# DDR4.net
KiCad netlist of a schematic drawn in Altium Designer
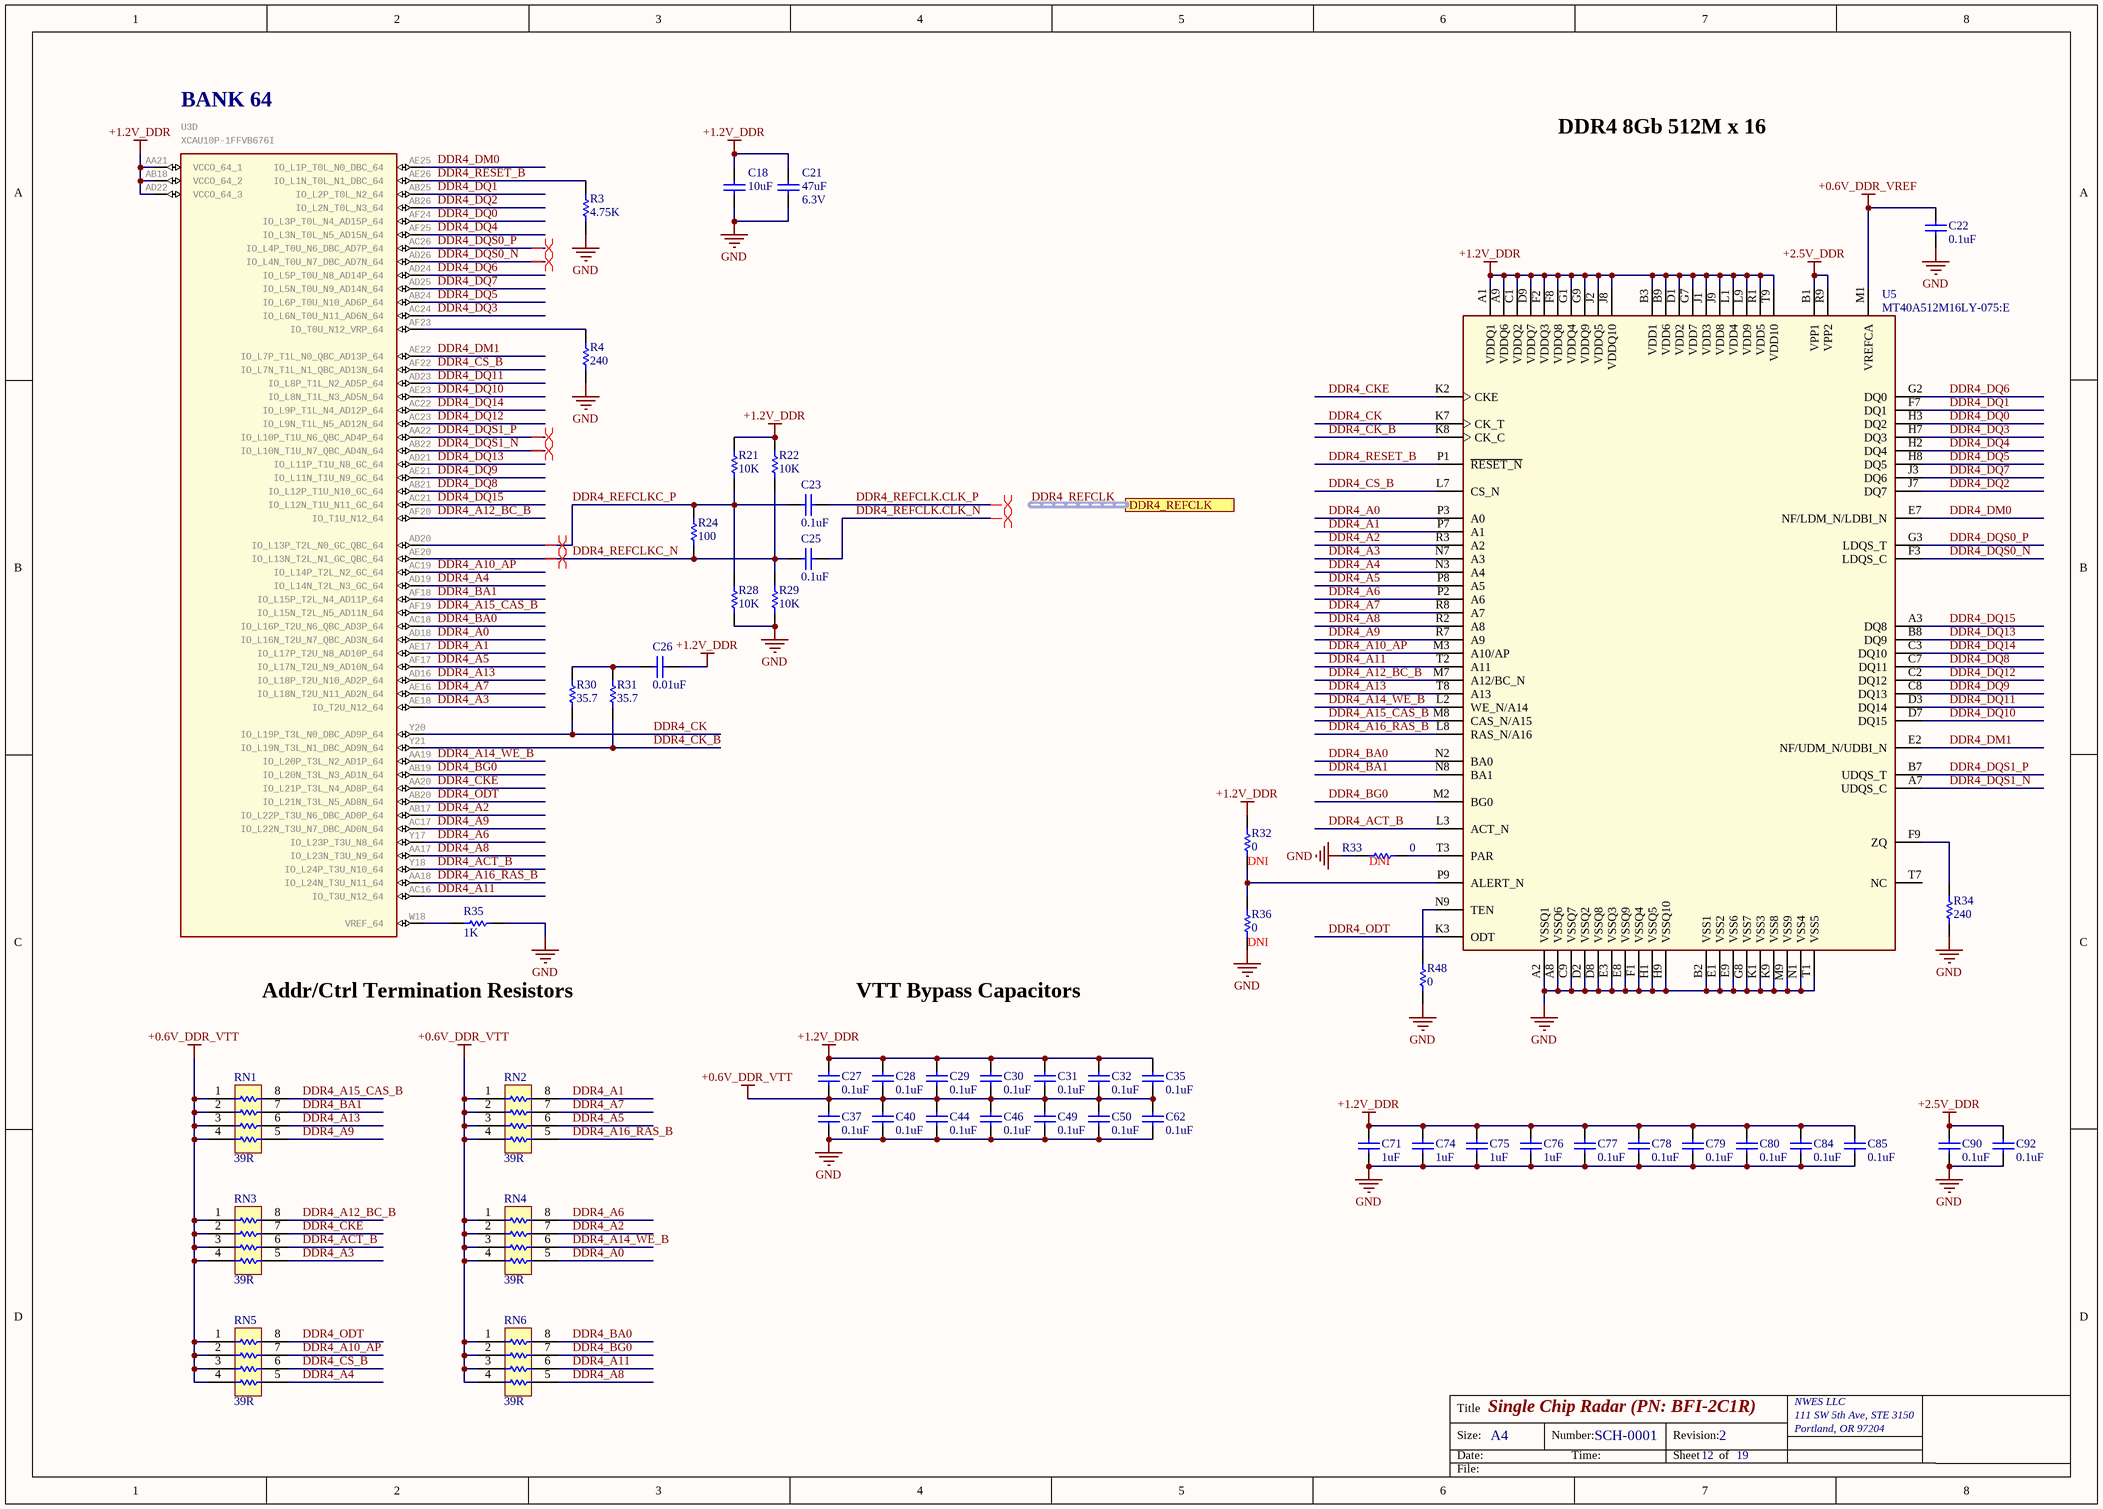
[diagram p0: DDR4.SchDoc]

(export (version "E")
  (design (tool "Eeschema 10.0.6"))
  (components
    (comp (ref "C18")
      (value "10uF")
      (footprint "CAPC1005X90")
      (description "CAP CER 10UF 10V X5R 0402")
      (fields
        (field (name "MANUFACTURER PART NUMBER") "CL05A106MP8NUB8")
        (field (name "MANUFACTURER") "Samsung Electro-Mechanics")
      )
      (libsource (lib "Radar FPGA RF") (part "CAP CER 10UF 10V X5R 0402"))
    )
    (comp (ref "C21")
      (value "47uF")
      (footprint "CAP-1206")
      (description "CAP CER 47UF 6.3V X5R 0805")
      (fields
        (field (name "MANUFACTURER") "Samsung")
        (field (name "MANUFACTURER PART NUMBER") "CL21A476MQYNNNE")
        (field (name "VOLTAGE RATING") "6.3V")
      )
      (libsource (lib "Radar FPGA RF") (part "CAP CER 47UF 6.3V X5R 0805"))
    )
    (comp (ref "C22")
      (value "0.1uF")
      (footprint "CAPC1005X55USR")
      (description "CAP CER 0.1UF 25V X5R 0402")
      (fields
        (field (name "MANUFACTURER PART NUMBER") "CL05A104KA5NNNC")
        (field (name "MANUFACTURER") "Samsung Electro-Mechanics")
      )
      (libsource (lib "Radar FPGA RF") (part "CAP CER 0.1UF 25V X5R 0402"))
    )
    (comp (ref "C23")
      (value "0.1uF")
      (footprint "CAPC1005X55USR")
      (description "CAP CER 0.1UF 25V X5R 0402")
      (fields
        (field (name "MANUFACTURER PART NUMBER") "CL05A104KA5NNNC")
        (field (name "MANUFACTURER") "Samsung Electro-Mechanics")
      )
      (libsource (lib "Radar FPGA RF") (part "CAP CER 0.1UF 25V X5R 0402"))
    )
    (comp (ref "C25")
      (value "0.1uF")
      (footprint "CAPC1005X55USR")
      (description "CAP CER 0.1UF 25V X5R 0402")
      (fields
        (field (name "MANUFACTURER PART NUMBER") "CL05A104KA5NNNC")
        (field (name "MANUFACTURER") "Samsung Electro-Mechanics")
      )
      (libsource (lib "Radar FPGA RF") (part "CAP CER 0.1UF 25V X5R 0402"))
    )
    (comp (ref "C26")
      (value "0.01uF")
      (footprint "CAPC1005X55USR")
      (description "CAP CER 10000PF 50V X7R 0402")
      (fields
        (field (name "MANUFACTURER PART NUMBER") "GCM155R71H103KA55D")
        (field (name "MANUFACTURER") "Murata Electronics")
      )
      (libsource (lib "Radar FPGA RF") (part "CAP CER 0.01uF 50V X7R 0402"))
    )
    (comp (ref "C27")
      (value "0.1uF")
      (footprint "CAPC1005X55USR")
      (description "CAP CER 0.1UF 25V X5R 0402")
      (fields
        (field (name "MANUFACTURER PART NUMBER") "CL05A104KA5NNNC")
        (field (name "MANUFACTURER") "Samsung Electro-Mechanics")
      )
      (libsource (lib "Radar FPGA RF") (part "CAP CER 0.1UF 25V X5R 0402"))
    )
    (comp (ref "C28")
      (value "0.1uF")
      (footprint "CAPC1005X55USR")
      (description "CAP CER 0.1UF 25V X5R 0402")
      (fields
        (field (name "MANUFACTURER PART NUMBER") "CL05A104KA5NNNC")
        (field (name "MANUFACTURER") "Samsung Electro-Mechanics")
      )
      (libsource (lib "Radar FPGA RF") (part "CAP CER 0.1UF 25V X5R 0402"))
    )
    (comp (ref "C29")
      (value "0.1uF")
      (footprint "CAPC1005X55USR")
      (description "CAP CER 0.1UF 25V X5R 0402")
      (fields
        (field (name "MANUFACTURER PART NUMBER") "CL05A104KA5NNNC")
        (field (name "MANUFACTURER") "Samsung Electro-Mechanics")
      )
      (libsource (lib "Radar FPGA RF") (part "CAP CER 0.1UF 25V X5R 0402"))
    )
    (comp (ref "C30")
      (value "0.1uF")
      (footprint "CAPC1005X55USR")
      (description "CAP CER 0.1UF 25V X5R 0402")
      (fields
        (field (name "MANUFACTURER PART NUMBER") "CL05A104KA5NNNC")
        (field (name "MANUFACTURER") "Samsung Electro-Mechanics")
      )
      (libsource (lib "Radar FPGA RF") (part "CAP CER 0.1UF 25V X5R 0402"))
    )
    (comp (ref "C31")
      (value "0.1uF")
      (footprint "CAPC1005X55USR")
      (description "CAP CER 0.1UF 25V X5R 0402")
      (fields
        (field (name "MANUFACTURER PART NUMBER") "CL05A104KA5NNNC")
        (field (name "MANUFACTURER") "Samsung Electro-Mechanics")
      )
      (libsource (lib "Radar FPGA RF") (part "CAP CER 0.1UF 25V X5R 0402"))
    )
    (comp (ref "C32")
      (value "0.1uF")
      (footprint "CAPC1005X55USR")
      (description "CAP CER 0.1UF 25V X5R 0402")
      (fields
        (field (name "MANUFACTURER PART NUMBER") "CL05A104KA5NNNC")
        (field (name "MANUFACTURER") "Samsung Electro-Mechanics")
      )
      (libsource (lib "Radar FPGA RF") (part "CAP CER 0.1UF 25V X5R 0402"))
    )
    (comp (ref "C35")
      (value "0.1uF")
      (footprint "CAPC1005X55USR")
      (description "CAP CER 0.1UF 25V X5R 0402")
      (fields
        (field (name "MANUFACTURER PART NUMBER") "CL05A104KA5NNNC")
        (field (name "MANUFACTURER") "Samsung Electro-Mechanics")
      )
      (libsource (lib "Radar FPGA RF") (part "CAP CER 0.1UF 25V X5R 0402"))
    )
    (comp (ref "C37")
      (value "0.1uF")
      (footprint "CAPC1005X55USR")
      (description "CAP CER 0.1UF 25V X5R 0402")
      (fields
        (field (name "MANUFACTURER PART NUMBER") "CL05A104KA5NNNC")
        (field (name "MANUFACTURER") "Samsung Electro-Mechanics")
      )
      (libsource (lib "Radar FPGA RF") (part "CAP CER 0.1UF 25V X5R 0402"))
    )
    (comp (ref "C40")
      (value "0.1uF")
      (footprint "CAPC1005X55USR")
      (description "CAP CER 0.1UF 25V X5R 0402")
      (fields
        (field (name "MANUFACTURER PART NUMBER") "CL05A104KA5NNNC")
        (field (name "MANUFACTURER") "Samsung Electro-Mechanics")
      )
      (libsource (lib "Radar FPGA RF") (part "CAP CER 0.1UF 25V X5R 0402"))
    )
    (comp (ref "C44")
      (value "0.1uF")
      (footprint "CAPC1005X55USR")
      (description "CAP CER 0.1UF 25V X5R 0402")
      (fields
        (field (name "MANUFACTURER PART NUMBER") "CL05A104KA5NNNC")
        (field (name "MANUFACTURER") "Samsung Electro-Mechanics")
      )
      (libsource (lib "Radar FPGA RF") (part "CAP CER 0.1UF 25V X5R 0402"))
    )
    (comp (ref "C46")
      (value "0.1uF")
      (footprint "CAPC1005X55USR")
      (description "CAP CER 0.1UF 25V X5R 0402")
      (fields
        (field (name "MANUFACTURER PART NUMBER") "CL05A104KA5NNNC")
        (field (name "MANUFACTURER") "Samsung Electro-Mechanics")
      )
      (libsource (lib "Radar FPGA RF") (part "CAP CER 0.1UF 25V X5R 0402"))
    )
    (comp (ref "C49")
      (value "0.1uF")
      (footprint "CAPC1005X55USR")
      (description "CAP CER 0.1UF 25V X5R 0402")
      (fields
        (field (name "MANUFACTURER PART NUMBER") "CL05A104KA5NNNC")
        (field (name "MANUFACTURER") "Samsung Electro-Mechanics")
      )
      (libsource (lib "Radar FPGA RF") (part "CAP CER 0.1UF 25V X5R 0402"))
    )
    (comp (ref "C50")
      (value "0.1uF")
      (footprint "CAPC1005X55USR")
      (description "CAP CER 0.1UF 25V X5R 0402")
      (fields
        (field (name "MANUFACTURER PART NUMBER") "CL05A104KA5NNNC")
        (field (name "MANUFACTURER") "Samsung Electro-Mechanics")
      )
      (libsource (lib "Radar FPGA RF") (part "CAP CER 0.1UF 25V X5R 0402"))
    )
    (comp (ref "C62")
      (value "0.1uF")
      (footprint "CAPC1005X55USR")
      (description "CAP CER 0.1UF 25V X5R 0402")
      (fields
        (field (name "MANUFACTURER PART NUMBER") "CL05A104KA5NNNC")
        (field (name "MANUFACTURER") "Samsung Electro-Mechanics")
      )
      (libsource (lib "Radar FPGA RF") (part "CAP CER 0.1UF 25V X5R 0402"))
    )
    (comp (ref "C71")
      (value "1uF")
      (footprint "CAPC1005X55USR")
      (description "CAP CER 1UF 25V X5R 0402")
      (fields
        (field (name "MANUFACTURER PART NUMBER") "GRM155R61E105MA12D")
        (field (name "MANUFACTURER") "Murata Electronics")
      )
      (libsource (lib "Radar FPGA RF") (part "CAP CER 1UF 25V X5R 0402"))
    )
    (comp (ref "C74")
      (value "1uF")
      (footprint "CAPC1005X55USR")
      (description "CAP CER 1UF 25V X5R 0402")
      (fields
        (field (name "MANUFACTURER PART NUMBER") "GRM155R61E105MA12D")
        (field (name "MANUFACTURER") "Murata Electronics")
      )
      (libsource (lib "Radar FPGA RF") (part "CAP CER 1UF 25V X5R 0402"))
    )
    (comp (ref "C75")
      (value "1uF")
      (footprint "CAPC1005X55USR")
      (description "CAP CER 1UF 25V X5R 0402")
      (fields
        (field (name "MANUFACTURER PART NUMBER") "GRM155R61E105MA12D")
        (field (name "MANUFACTURER") "Murata Electronics")
      )
      (libsource (lib "Radar FPGA RF") (part "CAP CER 1UF 25V X5R 0402"))
    )
    (comp (ref "C76")
      (value "1uF")
      (footprint "CAPC1005X55USR")
      (description "CAP CER 1UF 25V X5R 0402")
      (fields
        (field (name "MANUFACTURER PART NUMBER") "GRM155R61E105MA12D")
        (field (name "MANUFACTURER") "Murata Electronics")
      )
      (libsource (lib "Radar FPGA RF") (part "CAP CER 1UF 25V X5R 0402"))
    )
    (comp (ref "C77")
      (value "0.1uF")
      (footprint "CAPC1005X55USR")
      (description "CAP CER 0.1UF 25V X5R 0402")
      (fields
        (field (name "MANUFACTURER PART NUMBER") "CL05A104KA5NNNC")
        (field (name "MANUFACTURER") "Samsung Electro-Mechanics")
      )
      (libsource (lib "Radar FPGA RF") (part "CAP CER 0.1UF 25V X5R 0402"))
    )
    (comp (ref "C78")
      (value "0.1uF")
      (footprint "CAPC1005X55USR")
      (description "CAP CER 0.1UF 25V X5R 0402")
      (fields
        (field (name "MANUFACTURER PART NUMBER") "CL05A104KA5NNNC")
        (field (name "MANUFACTURER") "Samsung Electro-Mechanics")
      )
      (libsource (lib "Radar FPGA RF") (part "CAP CER 0.1UF 25V X5R 0402"))
    )
    (comp (ref "C79")
      (value "0.1uF")
      (footprint "CAPC1005X55USR")
      (description "CAP CER 0.1UF 25V X5R 0402")
      (fields
        (field (name "MANUFACTURER PART NUMBER") "CL05A104KA5NNNC")
        (field (name "MANUFACTURER") "Samsung Electro-Mechanics")
      )
      (libsource (lib "Radar FPGA RF") (part "CAP CER 0.1UF 25V X5R 0402"))
    )
    (comp (ref "C80")
      (value "0.1uF")
      (footprint "CAPC1005X55USR")
      (description "CAP CER 0.1UF 25V X5R 0402")
      (fields
        (field (name "MANUFACTURER PART NUMBER") "CL05A104KA5NNNC")
        (field (name "MANUFACTURER") "Samsung Electro-Mechanics")
      )
      (libsource (lib "Radar FPGA RF") (part "CAP CER 0.1UF 25V X5R 0402"))
    )
    (comp (ref "C84")
      (value "0.1uF")
      (footprint "CAPC1005X55USR")
      (description "CAP CER 0.1UF 25V X5R 0402")
      (fields
        (field (name "MANUFACTURER PART NUMBER") "CL05A104KA5NNNC")
        (field (name "MANUFACTURER") "Samsung Electro-Mechanics")
      )
      (libsource (lib "Radar FPGA RF") (part "CAP CER 0.1UF 25V X5R 0402"))
    )
    (comp (ref "C85")
      (value "0.1uF")
      (footprint "CAPC1005X55USR")
      (description "CAP CER 0.1UF 25V X5R 0402")
      (fields
        (field (name "MANUFACTURER PART NUMBER") "CL05A104KA5NNNC")
        (field (name "MANUFACTURER") "Samsung Electro-Mechanics")
      )
      (libsource (lib "Radar FPGA RF") (part "CAP CER 0.1UF 25V X5R 0402"))
    )
    (comp (ref "C90")
      (value "0.1uF")
      (footprint "CAPC1005X55USR")
      (description "CAP CER 0.1UF 25V X5R 0402")
      (fields
        (field (name "MANUFACTURER PART NUMBER") "CL05A104KA5NNNC")
        (field (name "MANUFACTURER") "Samsung Electro-Mechanics")
      )
      (libsource (lib "Radar FPGA RF") (part "CAP CER 0.1UF 25V X5R 0402"))
    )
    (comp (ref "C92")
      (value "0.1uF")
      (footprint "CAPC1005X55USR")
      (description "CAP CER 0.1UF 25V X5R 0402")
      (fields
        (field (name "MANUFACTURER PART NUMBER") "CL05A104KA5NNNC")
        (field (name "MANUFACTURER") "Samsung Electro-Mechanics")
      )
      (libsource (lib "Radar FPGA RF") (part "CAP CER 0.1UF 25V X5R 0402"))
    )
    (comp (ref "R3")
      (value "4.75K")
      (footprint "RESC1005X40USR")
      (description "RES 4.75K OHM 1% 1/16W 0402")
      (fields
        (field (name "MANUFACTURER") "YAGEO")
        (field (name "MANUFACTURER PART NUMBER") "RC0402FR-074K75L")
      )
      (libsource (lib "Radar FPGA RF") (part "RES 4.75K OHM 1% 1/16W 0402"))
    )
    (comp (ref "R4")
      (value "240")
      (footprint "RESC1005X40USR")
      (description "RES 240 OHM 1% 1/16W 0402")
      (fields
        (field (name "MANUFACTURER") "YAGEO")
        (field (name "MANUFACTURER PART NUMBER") "RC0402FR-07240RL")
      )
      (libsource (lib "Radar FPGA RF") (part "RES 240 OHM 1% 1/16W 0402"))
    )
    (comp (ref "R21")
      (value "10K")
      (footprint "RESC1005X40USR")
      (description "RES 10K OHM 1% 1/16W 0402")
      (fields
        (field (name "MANUFACTURER") "YAGEO")
        (field (name "MANUFACTURER PART NUMBER") "RC0402FR-0710KL")
      )
      (libsource (lib "Radar FPGA RF") (part "RES 10K OHM 1% 1/16W 0402"))
    )
    (comp (ref "R22")
      (value "10K")
      (footprint "RESC1005X40USR")
      (description "RES 10K OHM 1% 1/16W 0402")
      (fields
        (field (name "MANUFACTURER") "YAGEO")
        (field (name "MANUFACTURER PART NUMBER") "RC0402FR-0710KL")
      )
      (libsource (lib "Radar FPGA RF") (part "RES 10K OHM 1% 1/16W 0402"))
    )
    (comp (ref "R24")
      (value "100")
      (footprint "RESC1005X40USR")
      (description "RES 100 OHM 1% 1/16W 0402")
      (fields
        (field (name "MANUFACTURER") "YAGEO")
        (field (name "MANUFACTURER PART NUMBER") "RC0402FR-07100RL")
      )
      (libsource (lib "Radar FPGA RF") (part "RES 100 OHM 1% 1/16W 0402"))
    )
    (comp (ref "R28")
      (value "10K")
      (footprint "RESC1005X40USR")
      (description "RES 10K OHM 1% 1/16W 0402")
      (fields
        (field (name "MANUFACTURER") "YAGEO")
        (field (name "MANUFACTURER PART NUMBER") "RC0402FR-0710KL")
      )
      (libsource (lib "Radar FPGA RF") (part "RES 10K OHM 1% 1/16W 0402"))
    )
    (comp (ref "R29")
      (value "10K")
      (footprint "RESC1005X40USR")
      (description "RES 10K OHM 1% 1/16W 0402")
      (fields
        (field (name "MANUFACTURER") "YAGEO")
        (field (name "MANUFACTURER PART NUMBER") "RC0402FR-0710KL")
      )
      (libsource (lib "Radar FPGA RF") (part "RES 10K OHM 1% 1/16W 0402"))
    )
    (comp (ref "R30")
      (value "35.7")
      (footprint "RESC1005X40USR")
      (description "RES 35.7 OHM 1% 1/16W 0402")
      (fields
        (field (name "MANUFACTURER") "YAGEO")
        (field (name "MANUFACTURER PART NUMBER") "RC0402FR-0735R7L")
      )
      (libsource (lib "Radar FPGA RF") (part "RES 35.7 OHM 1% 1/16W 0402"))
    )
    (comp (ref "R31")
      (value "35.7")
      (footprint "RESC1005X40USR")
      (description "RES 35.7 OHM 1% 1/16W 0402")
      (fields
        (field (name "MANUFACTURER") "YAGEO")
        (field (name "MANUFACTURER PART NUMBER") "RC0402FR-0735R7L")
      )
      (libsource (lib "Radar FPGA RF") (part "RES 35.7 OHM 1% 1/16W 0402"))
    )
    (comp (ref "R32")
      (value "0")
      (footprint "RESC1005X40USR")
      (description "RES 0 OHM JUMPER 1/16W 0402")
      (fields
        (field (name "MANUFACTURER") "Yageo")
        (field (name "MANUFACTURER PART NUMBER") "RC0402JR-070RL")
      )
      (libsource (lib "Radar FPGA RF") (part "RES 0 OHM JUMPER 1/16W 0402"))
    )
    (comp (ref "R33")
      (value "0")
      (footprint "RESC1005X40USR")
      (description "RES 0 OHM JUMPER 1/16W 0402")
      (fields
        (field (name "MANUFACTURER") "Yageo")
        (field (name "MANUFACTURER PART NUMBER") "RC0402JR-070RL")
      )
      (libsource (lib "Radar FPGA RF") (part "RES 0 OHM JUMPER 1/16W 0402"))
    )
    (comp (ref "R34")
      (value "240")
      (footprint "RESC1005X40USR")
      (description "RES 240 OHM 1% 1/16W 0402")
      (fields
        (field (name "MANUFACTURER") "YAGEO")
        (field (name "MANUFACTURER PART NUMBER") "RC0402FR-07240RL")
      )
      (libsource (lib "Radar FPGA RF") (part "RES 240 OHM 1% 1/16W 0402"))
    )
    (comp (ref "R35")
      (value "1K")
      (footprint "RESC1005X40USR")
      (description "RES 1K OHM 1% 1/16W 0402")
      (fields
        (field (name "MANUFACTURER") "YAGEO")
        (field (name "MANUFACTURER PART NUMBER") "RC0402FR-071KL")
      )
      (libsource (lib "Radar FPGA RF") (part "RES 1K OHM 1% 1/16W 0402"))
    )
    (comp (ref "R36")
      (value "0")
      (footprint "RESC1005X40USR")
      (description "RES 0 OHM JUMPER 1/16W 0402")
      (fields
        (field (name "MANUFACTURER") "Yageo")
        (field (name "MANUFACTURER PART NUMBER") "RC0402JR-070RL")
      )
      (libsource (lib "Radar FPGA RF") (part "RES 0 OHM JUMPER 1/16W 0402"))
    )
    (comp (ref "R48")
      (value "0")
      (footprint "RESC1005X40USR")
      (description "RES 0 OHM JUMPER 1/16W 0402")
      (fields
        (field (name "MANUFACTURER") "Yageo")
        (field (name "MANUFACTURER PART NUMBER") "RC0402JR-070RL")
      )
      (libsource (lib "Radar FPGA RF") (part "RES 0 OHM JUMPER 1/16W 0402"))
    )
    (comp (ref "RN1")
      (value "39R")
      (footprint "RESCAXS50P100X200X45-8NA")
      (description "Res Thick Film Array 39 Ohm 5% ±200ppm/°C ISOL Molded 8-Pin 0804(4 X 0402) Concave SMD T/R")
      (fields
        (field (name "MANUFACTURER") "Panasonic")
        (field (name "MANUFACTURER PART NUMBER") "EXB-N8V390JX")
      )
      (libsource (lib "Radar FPGA RF") (part "RES ARRAY 4 RES 39 OHM 0804"))
    )
    (comp (ref "RN2")
      (value "39R")
      (footprint "RESCAXS50P100X200X45-8NA")
      (description "Res Thick Film Array 39 Ohm 5% ±200ppm/°C ISOL Molded 8-Pin 0804(4 X 0402) Concave SMD T/R")
      (fields
        (field (name "MANUFACTURER") "Panasonic")
        (field (name "MANUFACTURER PART NUMBER") "EXB-N8V390JX")
      )
      (libsource (lib "Radar FPGA RF") (part "RES ARRAY 4 RES 39 OHM 0804"))
    )
    (comp (ref "RN3")
      (value "39R")
      (footprint "RESCAXS50P100X200X45-8NA")
      (description "Res Thick Film Array 39 Ohm 5% ±200ppm/°C ISOL Molded 8-Pin 0804(4 X 0402) Concave SMD T/R")
      (fields
        (field (name "MANUFACTURER") "Panasonic")
        (field (name "MANUFACTURER PART NUMBER") "EXB-N8V390JX")
      )
      (libsource (lib "Radar FPGA RF") (part "RES ARRAY 4 RES 39 OHM 0804"))
    )
    (comp (ref "RN4")
      (value "39R")
      (footprint "RESCAXS50P100X200X45-8NA")
      (description "Res Thick Film Array 39 Ohm 5% ±200ppm/°C ISOL Molded 8-Pin 0804(4 X 0402) Concave SMD T/R")
      (fields
        (field (name "MANUFACTURER") "Panasonic")
        (field (name "MANUFACTURER PART NUMBER") "EXB-N8V390JX")
      )
      (libsource (lib "Radar FPGA RF") (part "RES ARRAY 4 RES 39 OHM 0804"))
    )
    (comp (ref "RN5")
      (value "39R")
      (footprint "RESCAXS50P100X200X45-8NA")
      (description "Res Thick Film Array 39 Ohm 5% ±200ppm/°C ISOL Molded 8-Pin 0804(4 X 0402) Concave SMD T/R")
      (fields
        (field (name "MANUFACTURER") "Panasonic")
        (field (name "MANUFACTURER PART NUMBER") "EXB-N8V390JX")
      )
      (libsource (lib "Radar FPGA RF") (part "RES ARRAY 4 RES 39 OHM 0804"))
    )
    (comp (ref "RN6")
      (value "39R")
      (footprint "RESCAXS50P100X200X45-8NA")
      (description "Res Thick Film Array 39 Ohm 5% ±200ppm/°C ISOL Molded 8-Pin 0804(4 X 0402) Concave SMD T/R")
      (fields
        (field (name "MANUFACTURER") "Panasonic")
        (field (name "MANUFACTURER PART NUMBER") "EXB-N8V390JX")
      )
      (libsource (lib "Radar FPGA RF") (part "RES ARRAY 4 RES 39 OHM 0804"))
    )
    (comp (ref "U3")
      (value "XCAU10P-1FFVB676I")
      (footprint "676-FCBGA (27x27)")
      (description "IC FPGA ARTIXUP 676BGA")
      (fields (field (name "MANUFACTURER") "AMD Xilinx"))
      (libsource (lib "LL") (part "XCAU10P-1FFVB676I"))
    )
    (comp (ref "U5")
      (value "MT40A512M16LY-075:E")
      (footprint "BGA96C80P6X16_1350X750X110")
      (description "DRAM Chip DDR4 SDRAM 8Gbit 512Mx16 1.2V 96-Pin FBGA Tray")
      (fields (field (name "MF") "Micron Technology"))
      (libsource (lib "XEM8320") (part "MT40A512M16LY-075{colon}E"))
    )
  )
  (nets
    (net (code "2") (name "+0.6V_DDR_VREF") (class "Default")
      (node (ref "C22") (pin "2") (pinfunction "2_2") (pintype "passive"))
      (node (ref "U5") (pin "M1") (pinfunction "VREFCA_M1") (pintype "passive"))
    )
    (net (code "3") (name "+0.6V_DDR_VTT") (class "Default")
      (node (ref "C27") (pin "1") (pinfunction "1_1") (pintype "passive"))
      (node (ref "C28") (pin "1") (pinfunction "1_1") (pintype "passive"))
      (node (ref "C29") (pin "1") (pinfunction "1_1") (pintype "passive"))
      (node (ref "C30") (pin "1") (pinfunction "1_1") (pintype "passive"))
      (node (ref "C31") (pin "1") (pinfunction "1_1") (pintype "passive"))
      (node (ref "C32") (pin "1") (pinfunction "1_1") (pintype "passive"))
      (node (ref "C35") (pin "1") (pinfunction "1_1") (pintype "passive"))
      (node (ref "C37") (pin "2") (pinfunction "2_2") (pintype "passive"))
      (node (ref "C40") (pin "2") (pinfunction "2_2") (pintype "passive"))
      (node (ref "C44") (pin "2") (pinfunction "2_2") (pintype "passive"))
      (node (ref "C46") (pin "2") (pinfunction "2_2") (pintype "passive"))
      (node (ref "C49") (pin "2") (pinfunction "2_2") (pintype "passive"))
      (node (ref "C50") (pin "2") (pinfunction "2_2") (pintype "passive"))
      (node (ref "C62") (pin "2") (pinfunction "2_2") (pintype "passive"))
      (node (ref "RN1") (pin "1") (pinfunction "1_1") (pintype "passive"))
      (node (ref "RN1") (pin "2") (pinfunction "2_2") (pintype "passive"))
      (node (ref "RN1") (pin "3") (pinfunction "3_3") (pintype "passive"))
      (node (ref "RN1") (pin "4") (pinfunction "4_4") (pintype "passive"))
      (node (ref "RN2") (pin "1") (pinfunction "1_1") (pintype "passive"))
      (node (ref "RN2") (pin "2") (pinfunction "2_2") (pintype "passive"))
      (node (ref "RN2") (pin "3") (pinfunction "3_3") (pintype "passive"))
      (node (ref "RN2") (pin "4") (pinfunction "4_4") (pintype "passive"))
      (node (ref "RN3") (pin "1") (pinfunction "1_1") (pintype "passive"))
      (node (ref "RN3") (pin "2") (pinfunction "2_2") (pintype "passive"))
      (node (ref "RN3") (pin "3") (pinfunction "3_3") (pintype "passive"))
      (node (ref "RN3") (pin "4") (pinfunction "4_4") (pintype "passive"))
      (node (ref "RN4") (pin "1") (pinfunction "1_1") (pintype "passive"))
      (node (ref "RN4") (pin "2") (pinfunction "2_2") (pintype "passive"))
      (node (ref "RN4") (pin "3") (pinfunction "3_3") (pintype "passive"))
      (node (ref "RN4") (pin "4") (pinfunction "4_4") (pintype "passive"))
      (node (ref "RN5") (pin "1") (pinfunction "1_1") (pintype "passive"))
      (node (ref "RN5") (pin "2") (pinfunction "2_2") (pintype "passive"))
      (node (ref "RN5") (pin "3") (pinfunction "3_3") (pintype "passive"))
      (node (ref "RN5") (pin "4") (pinfunction "4_4") (pintype "passive"))
      (node (ref "RN6") (pin "1") (pinfunction "1_1") (pintype "passive"))
      (node (ref "RN6") (pin "2") (pinfunction "2_2") (pintype "passive"))
      (node (ref "RN6") (pin "3") (pinfunction "3_3") (pintype "passive"))
      (node (ref "RN6") (pin "4") (pinfunction "4_4") (pintype "passive"))
    )
    (net (code "4") (name "+1.2V_DDR") (class "Default")
      (node (ref "C18") (pin "2") (pinfunction "2_2") (pintype "passive"))
      (node (ref "C21") (pin "1") (pinfunction "1_1") (pintype "passive"))
      (node (ref "C26") (pin "2") (pinfunction "2_2") (pintype "passive"))
      (node (ref "C27") (pin "2") (pinfunction "2_2") (pintype "passive"))
      (node (ref "C28") (pin "2") (pinfunction "2_2") (pintype "passive"))
      (node (ref "C29") (pin "2") (pinfunction "2_2") (pintype "passive"))
      (node (ref "C30") (pin "2") (pinfunction "2_2") (pintype "passive"))
      (node (ref "C31") (pin "2") (pinfunction "2_2") (pintype "passive"))
      (node (ref "C32") (pin "2") (pinfunction "2_2") (pintype "passive"))
      (node (ref "C35") (pin "2") (pinfunction "2_2") (pintype "passive"))
      (node (ref "C71") (pin "2") (pinfunction "2_2") (pintype "passive"))
      (node (ref "C74") (pin "2") (pinfunction "2_2") (pintype "passive"))
      (node (ref "C75") (pin "2") (pinfunction "2_2") (pintype "passive"))
      (node (ref "C76") (pin "2") (pinfunction "2_2") (pintype "passive"))
      (node (ref "C77") (pin "2") (pinfunction "2_2") (pintype "passive"))
      (node (ref "C78") (pin "2") (pinfunction "2_2") (pintype "passive"))
      (node (ref "C79") (pin "2") (pinfunction "2_2") (pintype "passive"))
      (node (ref "C80") (pin "2") (pinfunction "2_2") (pintype "passive"))
      (node (ref "C84") (pin "2") (pinfunction "2_2") (pintype "passive"))
      (node (ref "C85") (pin "2") (pinfunction "2_2") (pintype "passive"))
      (node (ref "R21") (pin "2") (pinfunction "2_2") (pintype "passive"))
      (node (ref "R22") (pin "2") (pinfunction "2_2") (pintype "passive"))
      (node (ref "R32") (pin "1") (pinfunction "1_1") (pintype "passive"))
      (node (ref "U3") (pin "AA21") (pinfunction "VCCO_64_1_AA21") (pintype "bidirectional"))
      (node (ref "U3") (pin "AB18") (pinfunction "VCCO_64_2_AB18") (pintype "bidirectional"))
      (node (ref "U3") (pin "AD22") (pinfunction "VCCO_64_3_AD22") (pintype "bidirectional"))
      (node (ref "U5") (pin "A1") (pinfunction "VDDQ1_A1") (pintype "passive"))
      (node (ref "U5") (pin "A9") (pinfunction "VDDQ6_A9") (pintype "passive"))
      (node (ref "U5") (pin "B3") (pinfunction "VDD1_B3") (pintype "passive"))
      (node (ref "U5") (pin "B9") (pinfunction "VDD6_B9") (pintype "passive"))
      (node (ref "U5") (pin "C1") (pinfunction "VDDQ2_C1") (pintype "passive"))
      (node (ref "U5") (pin "D1") (pinfunction "VDD2_D1") (pintype "passive"))
      (node (ref "U5") (pin "D9") (pinfunction "VDDQ7_D9") (pintype "passive"))
      (node (ref "U5") (pin "F2") (pinfunction "VDDQ3_F2") (pintype "passive"))
      (node (ref "U5") (pin "F8") (pinfunction "VDDQ8_F8") (pintype "passive"))
      (node (ref "U5") (pin "G1") (pinfunction "VDDQ4_G1") (pintype "passive"))
      (node (ref "U5") (pin "G7") (pinfunction "VDD7_G7") (pintype "passive"))
      (node (ref "U5") (pin "G9") (pinfunction "VDDQ9_G9") (pintype "passive"))
      (node (ref "U5") (pin "J1") (pinfunction "VDD3_J1") (pintype "passive"))
      (node (ref "U5") (pin "J2") (pinfunction "VDDQ5_J2") (pintype "passive"))
      (node (ref "U5") (pin "J8") (pinfunction "VDDQ10_J8") (pintype "passive"))
      (node (ref "U5") (pin "J9") (pinfunction "VDD8_J9") (pintype "passive"))
      (node (ref "U5") (pin "L1") (pinfunction "VDD4_L1") (pintype "passive"))
      (node (ref "U5") (pin "L9") (pinfunction "VDD9_L9") (pintype "passive"))
      (node (ref "U5") (pin "R1") (pinfunction "VDD5_R1") (pintype "passive"))
      (node (ref "U5") (pin "T9") (pinfunction "VDD10_T9") (pintype "passive"))
    )
    (net (code "5") (name "+2.5V_DDR") (class "Default")
      (node (ref "C90") (pin "2") (pinfunction "2_2") (pintype "passive"))
      (node (ref "C92") (pin "2") (pinfunction "2_2") (pintype "passive"))
      (node (ref "U5") (pin "B1") (pinfunction "VPP1_B1") (pintype "passive"))
      (node (ref "U5") (pin "R9") (pinfunction "VPP2_R9") (pintype "passive"))
    )
    (net (code "6") (name "/DDR4_A0") (class "Default")
      (node (ref "RN4") (pin "5") (pinfunction "5_5") (pintype "passive"))
      (node (ref "U3") (pin "AD18") (pinfunction "IO_L16N_T2U_N7_QBC_AD3N_64_AD18") (pintype "bidirectional"))
      (node (ref "U5") (pin "P3") (pinfunction "A0_P3") (pintype "passive"))
    )
    (net (code "7") (name "/DDR4_A1") (class "Default")
      (node (ref "RN2") (pin "8") (pinfunction "8_8") (pintype "passive"))
      (node (ref "U3") (pin "AE17") (pinfunction "IO_L17P_T2U_N8_AD10P_64_AE17") (pintype "bidirectional"))
      (node (ref "U5") (pin "P7") (pinfunction "A1_P7") (pintype "passive"))
    )
    (net (code "8") (name "/DDR4_A2") (class "Default")
      (node (ref "RN4") (pin "7") (pinfunction "7_7") (pintype "passive"))
      (node (ref "U3") (pin "AB17") (pinfunction "IO_L22P_T3U_N6_DBC_AD0P_64_AB17") (pintype "bidirectional"))
      (node (ref "U5") (pin "R3") (pinfunction "A2_R3") (pintype "passive"))
    )
    (net (code "9") (name "/DDR4_A3") (class "Default")
      (node (ref "RN3") (pin "5") (pinfunction "5_5") (pintype "passive"))
      (node (ref "U3") (pin "AE18") (pinfunction "IO_T2U_N12_64_AE18") (pintype "bidirectional"))
      (node (ref "U5") (pin "N7") (pinfunction "A3_N7") (pintype "passive"))
    )
    (net (code "10") (name "/DDR4_A4") (class "Default")
      (node (ref "RN5") (pin "5") (pinfunction "5_5") (pintype "passive"))
      (node (ref "U3") (pin "AD19") (pinfunction "IO_L14N_T2L_N3_GC_64_AD19") (pintype "bidirectional"))
      (node (ref "U5") (pin "N3") (pinfunction "A4_N3") (pintype "passive"))
    )
    (net (code "11") (name "/DDR4_A5") (class "Default")
      (node (ref "RN2") (pin "6") (pinfunction "6_6") (pintype "passive"))
      (node (ref "U3") (pin "AF17") (pinfunction "IO_L17N_T2U_N9_AD10N_64_AF17") (pintype "bidirectional"))
      (node (ref "U5") (pin "P8") (pinfunction "A5_P8") (pintype "passive"))
    )
    (net (code "12") (name "/DDR4_A6") (class "Default")
      (node (ref "RN4") (pin "8") (pinfunction "8_8") (pintype "passive"))
      (node (ref "U3") (pin "Y17") (pinfunction "IO_L23P_T3U_N8_64_Y17") (pintype "bidirectional"))
      (node (ref "U5") (pin "P2") (pinfunction "A6_P2") (pintype "passive"))
    )
    (net (code "13") (name "/DDR4_A7") (class "Default")
      (node (ref "RN2") (pin "7") (pinfunction "7_7") (pintype "passive"))
      (node (ref "U3") (pin "AE16") (pinfunction "IO_L18N_T2U_N11_AD2N_64_AE16") (pintype "bidirectional"))
      (node (ref "U5") (pin "R8") (pinfunction "A7_R8") (pintype "passive"))
    )
    (net (code "14") (name "/DDR4_A8") (class "Default")
      (node (ref "RN6") (pin "5") (pinfunction "5_5") (pintype "passive"))
      (node (ref "U3") (pin "AA17") (pinfunction "IO_L23N_T3U_N9_64_AA17") (pintype "bidirectional"))
      (node (ref "U5") (pin "R2") (pinfunction "A8_R2") (pintype "passive"))
    )
    (net (code "15") (name "/DDR4_A9") (class "Default")
      (node (ref "RN1") (pin "5") (pinfunction "5_5") (pintype "passive"))
      (node (ref "U3") (pin "AC17") (pinfunction "IO_L22N_T3U_N7_DBC_AD0N_64_AC17") (pintype "bidirectional"))
      (node (ref "U5") (pin "R7") (pinfunction "A9_R7") (pintype "passive"))
    )
    (net (code "16") (name "/DDR4_A10_AP") (class "Default")
      (node (ref "RN5") (pin "7") (pinfunction "7_7") (pintype "passive"))
      (node (ref "U3") (pin "AC19") (pinfunction "IO_L14P_T2L_N2_GC_64_AC19") (pintype "bidirectional"))
      (node (ref "U5") (pin "M3") (pinfunction "A10/AP_M3") (pintype "passive"))
    )
    (net (code "17") (name "/DDR4_A11") (class "Default")
      (node (ref "RN6") (pin "6") (pinfunction "6_6") (pintype "passive"))
      (node (ref "U3") (pin "AC16") (pinfunction "IO_T3U_N12_64_AC16") (pintype "bidirectional"))
      (node (ref "U5") (pin "T2") (pinfunction "A11_T2") (pintype "passive"))
    )
    (net (code "18") (name "/DDR4_A12_BC_B") (class "Default")
      (node (ref "RN3") (pin "8") (pinfunction "8_8") (pintype "passive"))
      (node (ref "U3") (pin "AF20") (pinfunction "IO_T1U_N12_64_AF20") (pintype "bidirectional"))
      (node (ref "U5") (pin "M7") (pinfunction "A12/BC_N_M7") (pintype "passive"))
    )
    (net (code "19") (name "/DDR4_A13") (class "Default")
      (node (ref "RN1") (pin "6") (pinfunction "6_6") (pintype "passive"))
      (node (ref "U3") (pin "AD16") (pinfunction "IO_L18P_T2U_N10_AD2P_64_AD16") (pintype "bidirectional"))
      (node (ref "U5") (pin "T8") (pinfunction "A13_T8") (pintype "passive"))
    )
    (net (code "20") (name "/DDR4_A14_WE_B") (class "Default")
      (node (ref "RN4") (pin "6") (pinfunction "6_6") (pintype "passive"))
      (node (ref "U3") (pin "AA19") (pinfunction "IO_L20P_T3L_N2_AD1P_64_AA19") (pintype "bidirectional"))
      (node (ref "U5") (pin "L2") (pinfunction "WE_N/A14_L2") (pintype "passive"))
    )
    (net (code "21") (name "/DDR4_A15_CAS_B") (class "Default")
      (node (ref "RN1") (pin "8") (pinfunction "8_8") (pintype "passive"))
      (node (ref "U3") (pin "AF19") (pinfunction "IO_L15N_T2L_N5_AD11N_64_AF19") (pintype "bidirectional"))
      (node (ref "U5") (pin "M8") (pinfunction "CAS_N/A15_M8") (pintype "passive"))
    )
    (net (code "22") (name "/DDR4_A16_RAS_B") (class "Default")
      (node (ref "RN2") (pin "5") (pinfunction "5_5") (pintype "passive"))
      (node (ref "U3") (pin "AA18") (pinfunction "IO_L24N_T3U_N11_64_AA18") (pintype "bidirectional"))
      (node (ref "U5") (pin "L8") (pinfunction "RAS_N/A16_L8") (pintype "passive"))
    )
    (net (code "23") (name "/DDR4_ACT_B") (class "Default")
      (node (ref "RN3") (pin "6") (pinfunction "6_6") (pintype "passive"))
      (node (ref "U3") (pin "Y18") (pinfunction "IO_L24P_T3U_N10_64_Y18") (pintype "bidirectional"))
      (node (ref "U5") (pin "L3") (pinfunction "ACT_N_L3") (pintype "passive"))
    )
    (net (code "24") (name "/DDR4_BA0") (class "Default")
      (node (ref "RN6") (pin "8") (pinfunction "8_8") (pintype "passive"))
      (node (ref "U3") (pin "AC18") (pinfunction "IO_L16P_T2U_N6_QBC_AD3P_64_AC18") (pintype "bidirectional"))
      (node (ref "U5") (pin "N2") (pinfunction "BA0_N2") (pintype "passive"))
    )
    (net (code "25") (name "/DDR4_BA1") (class "Default")
      (node (ref "RN1") (pin "7") (pinfunction "7_7") (pintype "passive"))
      (node (ref "U3") (pin "AF18") (pinfunction "IO_L15P_T2L_N4_AD11P_64_AF18") (pintype "bidirectional"))
      (node (ref "U5") (pin "N8") (pinfunction "BA1_N8") (pintype "passive"))
    )
    (net (code "26") (name "/DDR4_BG0") (class "Default")
      (node (ref "RN6") (pin "7") (pinfunction "7_7") (pintype "passive"))
      (node (ref "U3") (pin "AB19") (pinfunction "IO_L20N_T3L_N3_AD1N_64_AB19") (pintype "bidirectional"))
      (node (ref "U5") (pin "M2") (pinfunction "BG0_M2") (pintype "passive"))
    )
    (net (code "27") (name "/DDR4_CK") (class "Default")
      (node (ref "R30") (pin "1") (pinfunction "1_1") (pintype "passive"))
      (node (ref "U3") (pin "Y20") (pinfunction "IO_L19P_T3L_N0_DBC_AD9P_64_Y20") (pintype "bidirectional"))
      (node (ref "U5") (pin "K7") (pinfunction "CK_T_K7") (pintype "passive"))
    )
    (net (code "28") (name "/DDR4_CKE") (class "Default")
      (node (ref "RN3") (pin "7") (pinfunction "7_7") (pintype "passive"))
      (node (ref "U3") (pin "AA20") (pinfunction "IO_L21P_T3L_N4_AD8P_64_AA20") (pintype "bidirectional"))
      (node (ref "U5") (pin "K2") (pinfunction "CKE_K2") (pintype "passive"))
    )
    (net (code "29") (name "/DDR4_CK_B") (class "Default")
      (node (ref "R31") (pin "1") (pinfunction "1_1") (pintype "passive"))
      (node (ref "U3") (pin "Y21") (pinfunction "IO_L19N_T3L_N1_DBC_AD9N_64_Y21") (pintype "bidirectional"))
      (node (ref "U5") (pin "K8") (pinfunction "CK_C_K8") (pintype "passive"))
    )
    (net (code "30") (name "/DDR4_CS_B") (class "Default")
      (node (ref "RN5") (pin "6") (pinfunction "6_6") (pintype "passive"))
      (node (ref "U3") (pin "AF22") (pinfunction "IO_L7N_T1L_N1_QBC_AD13N_64_AF22") (pintype "bidirectional"))
      (node (ref "U5") (pin "L7") (pinfunction "CS_N_L7") (pintype "passive"))
    )
    (net (code "31") (name "/DDR4_DM0") (class "Default")
      (node (ref "U3") (pin "AE25") (pinfunction "IO_L1P_T0L_N0_DBC_64_AE25") (pintype "bidirectional"))
      (node (ref "U5") (pin "E7") (pinfunction "NF/LDM_N/LDBI_N_E7") (pintype "passive"))
    )
    (net (code "32") (name "/DDR4_DM1") (class "Default")
      (node (ref "U3") (pin "AE22") (pinfunction "IO_L7P_T1L_N0_QBC_AD13P_64_AE22") (pintype "bidirectional"))
      (node (ref "U5") (pin "E2") (pinfunction "NF/UDM_N/UDBI_N_E2") (pintype "passive"))
    )
    (net (code "33") (name "/DDR4_DQ0") (class "Default")
      (node (ref "U3") (pin "AF24") (pinfunction "IO_L3P_T0L_N4_AD15P_64_AF24") (pintype "bidirectional"))
      (node (ref "U5") (pin "H3") (pinfunction "DQ2_H3") (pintype "passive"))
    )
    (net (code "34") (name "/DDR4_DQ1") (class "Default")
      (node (ref "U3") (pin "AB25") (pinfunction "IO_L2P_T0L_N2_64_AB25") (pintype "bidirectional"))
      (node (ref "U5") (pin "F7") (pinfunction "DQ1_F7") (pintype "passive"))
    )
    (net (code "35") (name "/DDR4_DQ2") (class "Default")
      (node (ref "U3") (pin "AB26") (pinfunction "IO_L2N_T0L_N3_64_AB26") (pintype "bidirectional"))
      (node (ref "U5") (pin "J7") (pinfunction "DQ7_J7") (pintype "passive"))
    )
    (net (code "36") (name "/DDR4_DQ3") (class "Default")
      (node (ref "U3") (pin "AC24") (pinfunction "IO_L6N_T0U_N11_AD6N_64_AC24") (pintype "bidirectional"))
      (node (ref "U5") (pin "H7") (pinfunction "DQ3_H7") (pintype "passive"))
    )
    (net (code "37") (name "/DDR4_DQ4") (class "Default")
      (node (ref "U3") (pin "AF25") (pinfunction "IO_L3N_T0L_N5_AD15N_64_AF25") (pintype "bidirectional"))
      (node (ref "U5") (pin "H2") (pinfunction "DQ4_H2") (pintype "passive"))
    )
    (net (code "38") (name "/DDR4_DQ5") (class "Default")
      (node (ref "U3") (pin "AB24") (pinfunction "IO_L6P_T0U_N10_AD6P_64_AB24") (pintype "bidirectional"))
      (node (ref "U5") (pin "H8") (pinfunction "DQ5_H8") (pintype "passive"))
    )
    (net (code "39") (name "/DDR4_DQ6") (class "Default")
      (node (ref "U3") (pin "AD24") (pinfunction "IO_L5P_T0U_N8_AD14P_64_AD24") (pintype "bidirectional"))
      (node (ref "U5") (pin "G2") (pinfunction "DQ0_G2") (pintype "passive"))
    )
    (net (code "40") (name "/DDR4_DQ7") (class "Default")
      (node (ref "U3") (pin "AD25") (pinfunction "IO_L5N_T0U_N9_AD14N_64_AD25") (pintype "bidirectional"))
      (node (ref "U5") (pin "J3") (pinfunction "DQ6_J3") (pintype "passive"))
    )
    (net (code "41") (name "/DDR4_DQ8") (class "Default")
      (node (ref "U3") (pin "AB21") (pinfunction "IO_L12P_T1U_N10_GC_64_AB21") (pintype "bidirectional"))
      (node (ref "U5") (pin "C7") (pinfunction "DQ11_C7") (pintype "passive"))
    )
    (net (code "42") (name "/DDR4_DQ9") (class "Default")
      (node (ref "U3") (pin "AE21") (pinfunction "IO_L11N_T1U_N9_GC_64_AE21") (pintype "bidirectional"))
      (node (ref "U5") (pin "C8") (pinfunction "DQ13_C8") (pintype "passive"))
    )
    (net (code "43") (name "/DDR4_DQ10") (class "Default")
      (node (ref "U3") (pin "AE23") (pinfunction "IO_L8N_T1L_N3_AD5N_64_AE23") (pintype "bidirectional"))
      (node (ref "U5") (pin "D7") (pinfunction "DQ15_D7") (pintype "passive"))
    )
    (net (code "44") (name "/DDR4_DQ11") (class "Default")
      (node (ref "U3") (pin "AD23") (pinfunction "IO_L8P_T1L_N2_AD5P_64_AD23") (pintype "bidirectional"))
      (node (ref "U5") (pin "D3") (pinfunction "DQ14_D3") (pintype "passive"))
    )
    (net (code "45") (name "/DDR4_DQ12") (class "Default")
      (node (ref "U3") (pin "AC23") (pinfunction "IO_L9N_T1L_N5_AD12N_64_AC23") (pintype "bidirectional"))
      (node (ref "U5") (pin "C2") (pinfunction "DQ12_C2") (pintype "passive"))
    )
    (net (code "46") (name "/DDR4_DQ13") (class "Default")
      (node (ref "U3") (pin "AD21") (pinfunction "IO_L11P_T1U_N8_GC_64_AD21") (pintype "bidirectional"))
      (node (ref "U5") (pin "B8") (pinfunction "DQ9_B8") (pintype "passive"))
    )
    (net (code "47") (name "/DDR4_DQ14") (class "Default")
      (node (ref "U3") (pin "AC22") (pinfunction "IO_L9P_T1L_N4_AD12P_64_AC22") (pintype "bidirectional"))
      (node (ref "U5") (pin "C3") (pinfunction "DQ10_C3") (pintype "passive"))
    )
    (net (code "48") (name "/DDR4_DQ15") (class "Default")
      (node (ref "U3") (pin "AC21") (pinfunction "IO_L12N_T1U_N11_GC_64_AC21") (pintype "bidirectional"))
      (node (ref "U5") (pin "A3") (pinfunction "DQ8_A3") (pintype "passive"))
    )
    (net (code "49") (name "/DDR4_DQS0_N") (class "Default")
      (node (ref "U3") (pin "AD26") (pinfunction "IO_L4N_T0U_N7_DBC_AD7N_64_AD26") (pintype "bidirectional"))
      (node (ref "U5") (pin "F3") (pinfunction "LDQS_C_F3") (pintype "passive"))
    )
    (net (code "50") (name "/DDR4_DQS0_P") (class "Default")
      (node (ref "U3") (pin "AC26") (pinfunction "IO_L4P_T0U_N6_DBC_AD7P_64_AC26") (pintype "bidirectional"))
      (node (ref "U5") (pin "G3") (pinfunction "LDQS_T_G3") (pintype "passive"))
    )
    (net (code "51") (name "/DDR4_DQS1_N") (class "Default")
      (node (ref "U3") (pin "AB22") (pinfunction "IO_L10N_T1U_N7_QBC_AD4N_64_AB22") (pintype "bidirectional"))
      (node (ref "U5") (pin "A7") (pinfunction "UDQS_C_A7") (pintype "passive"))
    )
    (net (code "52") (name "/DDR4_DQS1_P") (class "Default")
      (node (ref "U3") (pin "AA22") (pinfunction "IO_L10P_T1U_N6_QBC_AD4P_64_AA22") (pintype "bidirectional"))
      (node (ref "U5") (pin "B7") (pinfunction "UDQS_T_B7") (pintype "passive"))
    )
    (net (code "53") (name "/DDR4_ODT") (class "Default")
      (node (ref "RN5") (pin "8") (pinfunction "8_8") (pintype "passive"))
      (node (ref "U3") (pin "AB20") (pinfunction "IO_L21N_T3L_N5_AD8N_64_AB20") (pintype "bidirectional"))
      (node (ref "U5") (pin "K3") (pinfunction "ODT_K3") (pintype "passive"))
    )
    (net (code "54") (name "/DDR4_REFCLK.CLK_N") (class "Default")
      (node (ref "C25") (pin "1") (pinfunction "1_1") (pintype "passive"))
    )
    (net (code "55") (name "/DDR4_REFCLK.CLK_P") (class "Default")
      (node (ref "C23") (pin "1") (pinfunction "1_1") (pintype "passive"))
    )
    (net (code "56") (name "/DDR4_REFCLKC_N") (class "Default")
      (node (ref "C25") (pin "2") (pinfunction "2_2") (pintype "passive"))
      (node (ref "R22") (pin "1") (pinfunction "1_1") (pintype "passive"))
      (node (ref "R24") (pin "1") (pinfunction "1_1") (pintype "passive"))
      (node (ref "R29") (pin "2") (pinfunction "2_2") (pintype "passive"))
      (node (ref "U3") (pin "AE20") (pinfunction "IO_L13N_T2L_N1_GC_QBC_64_AE20") (pintype "bidirectional"))
    )
    (net (code "57") (name "/DDR4_REFCLKC_P") (class "Default")
      (node (ref "C23") (pin "2") (pinfunction "2_2") (pintype "passive"))
      (node (ref "R21") (pin "1") (pinfunction "1_1") (pintype "passive"))
      (node (ref "R24") (pin "2") (pinfunction "2_2") (pintype "passive"))
      (node (ref "R28") (pin "2") (pinfunction "2_2") (pintype "passive"))
      (node (ref "U3") (pin "AD20") (pinfunction "IO_L13P_T2L_N0_GC_QBC_64_AD20") (pintype "bidirectional"))
    )
    (net (code "58") (name "/DDR4_RESET_B") (class "Default")
      (node (ref "R3") (pin "2") (pinfunction "2_2") (pintype "passive"))
      (node (ref "U3") (pin "AE26") (pinfunction "IO_L1N_T0L_N1_DBC_64_AE26") (pintype "bidirectional"))
      (node (ref "U5") (pin "P1") (pinfunction "~{RESET_N}_P1") (pintype "passive"))
    )
    (net (code "60") (name "GND") (class "Default")
      (node (ref "C18") (pin "1") (pinfunction "1_1") (pintype "passive"))
      (node (ref "C21") (pin "2") (pinfunction "2_2") (pintype "passive"))
      (node (ref "C22") (pin "1") (pinfunction "1_1") (pintype "passive"))
      (node (ref "C37") (pin "1") (pinfunction "1_1") (pintype "passive"))
      (node (ref "C40") (pin "1") (pinfunction "1_1") (pintype "passive"))
      (node (ref "C44") (pin "1") (pinfunction "1_1") (pintype "passive"))
      (node (ref "C46") (pin "1") (pinfunction "1_1") (pintype "passive"))
      (node (ref "C49") (pin "1") (pinfunction "1_1") (pintype "passive"))
      (node (ref "C50") (pin "1") (pinfunction "1_1") (pintype "passive"))
      (node (ref "C62") (pin "1") (pinfunction "1_1") (pintype "passive"))
      (node (ref "C71") (pin "1") (pinfunction "1_1") (pintype "passive"))
      (node (ref "C74") (pin "1") (pinfunction "1_1") (pintype "passive"))
      (node (ref "C75") (pin "1") (pinfunction "1_1") (pintype "passive"))
      (node (ref "C76") (pin "1") (pinfunction "1_1") (pintype "passive"))
      (node (ref "C77") (pin "1") (pinfunction "1_1") (pintype "passive"))
      (node (ref "C78") (pin "1") (pinfunction "1_1") (pintype "passive"))
      (node (ref "C79") (pin "1") (pinfunction "1_1") (pintype "passive"))
      (node (ref "C80") (pin "1") (pinfunction "1_1") (pintype "passive"))
      (node (ref "C84") (pin "1") (pinfunction "1_1") (pintype "passive"))
      (node (ref "C85") (pin "1") (pinfunction "1_1") (pintype "passive"))
      (node (ref "C90") (pin "1") (pinfunction "1_1") (pintype "passive"))
      (node (ref "C92") (pin "1") (pinfunction "1_1") (pintype "passive"))
      (node (ref "R28") (pin "1") (pinfunction "1_1") (pintype "passive"))
      (node (ref "R29") (pin "1") (pinfunction "1_1") (pintype "passive"))
      (node (ref "R3") (pin "1") (pinfunction "1_1") (pintype "passive"))
      (node (ref "R33") (pin "2") (pinfunction "2_2") (pintype "passive"))
      (node (ref "R34") (pin "1") (pinfunction "1_1") (pintype "passive"))
      (node (ref "R35") (pin "2") (pinfunction "2_2") (pintype "passive"))
      (node (ref "R36") (pin "2") (pinfunction "2_2") (pintype "passive"))
      (node (ref "R4") (pin "1") (pinfunction "1_1") (pintype "passive"))
      (node (ref "R48") (pin "1") (pinfunction "1_1") (pintype "passive"))
      (node (ref "U5") (pin "A2") (pinfunction "VSSQ1_A2") (pintype "passive"))
      (node (ref "U5") (pin "A8") (pinfunction "VSSQ6_A8") (pintype "passive"))
      (node (ref "U5") (pin "B2") (pinfunction "VSS1_B2") (pintype "passive"))
      (node (ref "U5") (pin "C9") (pinfunction "VSSQ7_C9") (pintype "passive"))
      (node (ref "U5") (pin "D2") (pinfunction "VSSQ2_D2") (pintype "passive"))
      (node (ref "U5") (pin "D8") (pinfunction "VSSQ8_D8") (pintype "passive"))
      (node (ref "U5") (pin "E1") (pinfunction "VSS2_E1") (pintype "passive"))
      (node (ref "U5") (pin "E3") (pinfunction "VSSQ3_E3") (pintype "passive"))
      (node (ref "U5") (pin "E8") (pinfunction "VSSQ9_E8") (pintype "passive"))
      (node (ref "U5") (pin "E9") (pinfunction "VSS6_E9") (pintype "passive"))
      (node (ref "U5") (pin "F1") (pinfunction "VSSQ4_F1") (pintype "passive"))
      (node (ref "U5") (pin "G8") (pinfunction "VSS7_G8") (pintype "passive"))
      (node (ref "U5") (pin "H1") (pinfunction "VSSQ5_H1") (pintype "passive"))
      (node (ref "U5") (pin "H9") (pinfunction "VSSQ10_H9") (pintype "passive"))
      (node (ref "U5") (pin "K1") (pinfunction "VSS3_K1") (pintype "passive"))
      (node (ref "U5") (pin "K9") (pinfunction "VSS8_K9") (pintype "passive"))
      (node (ref "U5") (pin "M9") (pinfunction "VSS9_M9") (pintype "passive"))
      (node (ref "U5") (pin "N1") (pinfunction "VSS4_N1") (pintype "passive"))
      (node (ref "U5") (pin "T1") (pinfunction "VSS5_T1") (pintype "passive"))
    )
    (net (code "61") (name "Net-(C26-Pad1)") (class "Default")
      (node (ref "C26") (pin "1") (pinfunction "1_1") (pintype "passive"))
      (node (ref "R30") (pin "2") (pinfunction "2_2") (pintype "passive"))
      (node (ref "R31") (pin "2") (pinfunction "2_2") (pintype "passive"))
    )
    (net (code "62") (name "Net-(U3D-IO_T0U_N12_VRP_64)") (class "Default")
      (node (ref "R4") (pin "2") (pinfunction "2_2") (pintype "passive"))
      (node (ref "U3") (pin "AF23") (pinfunction "IO_T0U_N12_VRP_64_AF23") (pintype "bidirectional"))
    )
    (net (code "63") (name "Net-(U3D-VREF_64)") (class "Default")
      (node (ref "R35") (pin "1") (pinfunction "1_1") (pintype "passive"))
      (node (ref "U3") (pin "W18") (pinfunction "VREF_64_W18") (pintype "bidirectional"))
    )
    (net (code "64") (name "Net-(U5-ALERT_N)") (class "Default")
      (node (ref "R32") (pin "2") (pinfunction "2_2") (pintype "passive"))
      (node (ref "R36") (pin "1") (pinfunction "1_1") (pintype "passive"))
      (node (ref "U5") (pin "P9") (pinfunction "ALERT_N_P9") (pintype "passive"))
    )
    (net (code "65") (name "Net-(U5-PAR)") (class "Default")
      (node (ref "R33") (pin "1") (pinfunction "1_1") (pintype "passive"))
      (node (ref "U5") (pin "T3") (pinfunction "PAR_T3") (pintype "passive"))
    )
    (net (code "66") (name "Net-(U5-TEN)") (class "Default")
      (node (ref "R48") (pin "2") (pinfunction "2_2") (pintype "passive"))
      (node (ref "U5") (pin "N9") (pinfunction "TEN_N9") (pintype "passive"))
    )
    (net (code "67") (name "Net-(U5-ZQ)") (class "Default")
      (node (ref "R34") (pin "2") (pinfunction "2_2") (pintype "passive"))
      (node (ref "U5") (pin "F9") (pinfunction "ZQ_F9") (pintype "passive"))
    )
    (net (code "68") (name "unconnected-(U5-NC-PadT7)") (class "Default")
      (node (ref "U5") (pin "T7") (pinfunction "NC_T7") (pintype "passive"))
    )
  )
)
